# S7CAS-PLEIADES-CARTE-MERE_P01_FPGA-BANK0.net
KiCad netlist of a schematic drawn in Altium Designer
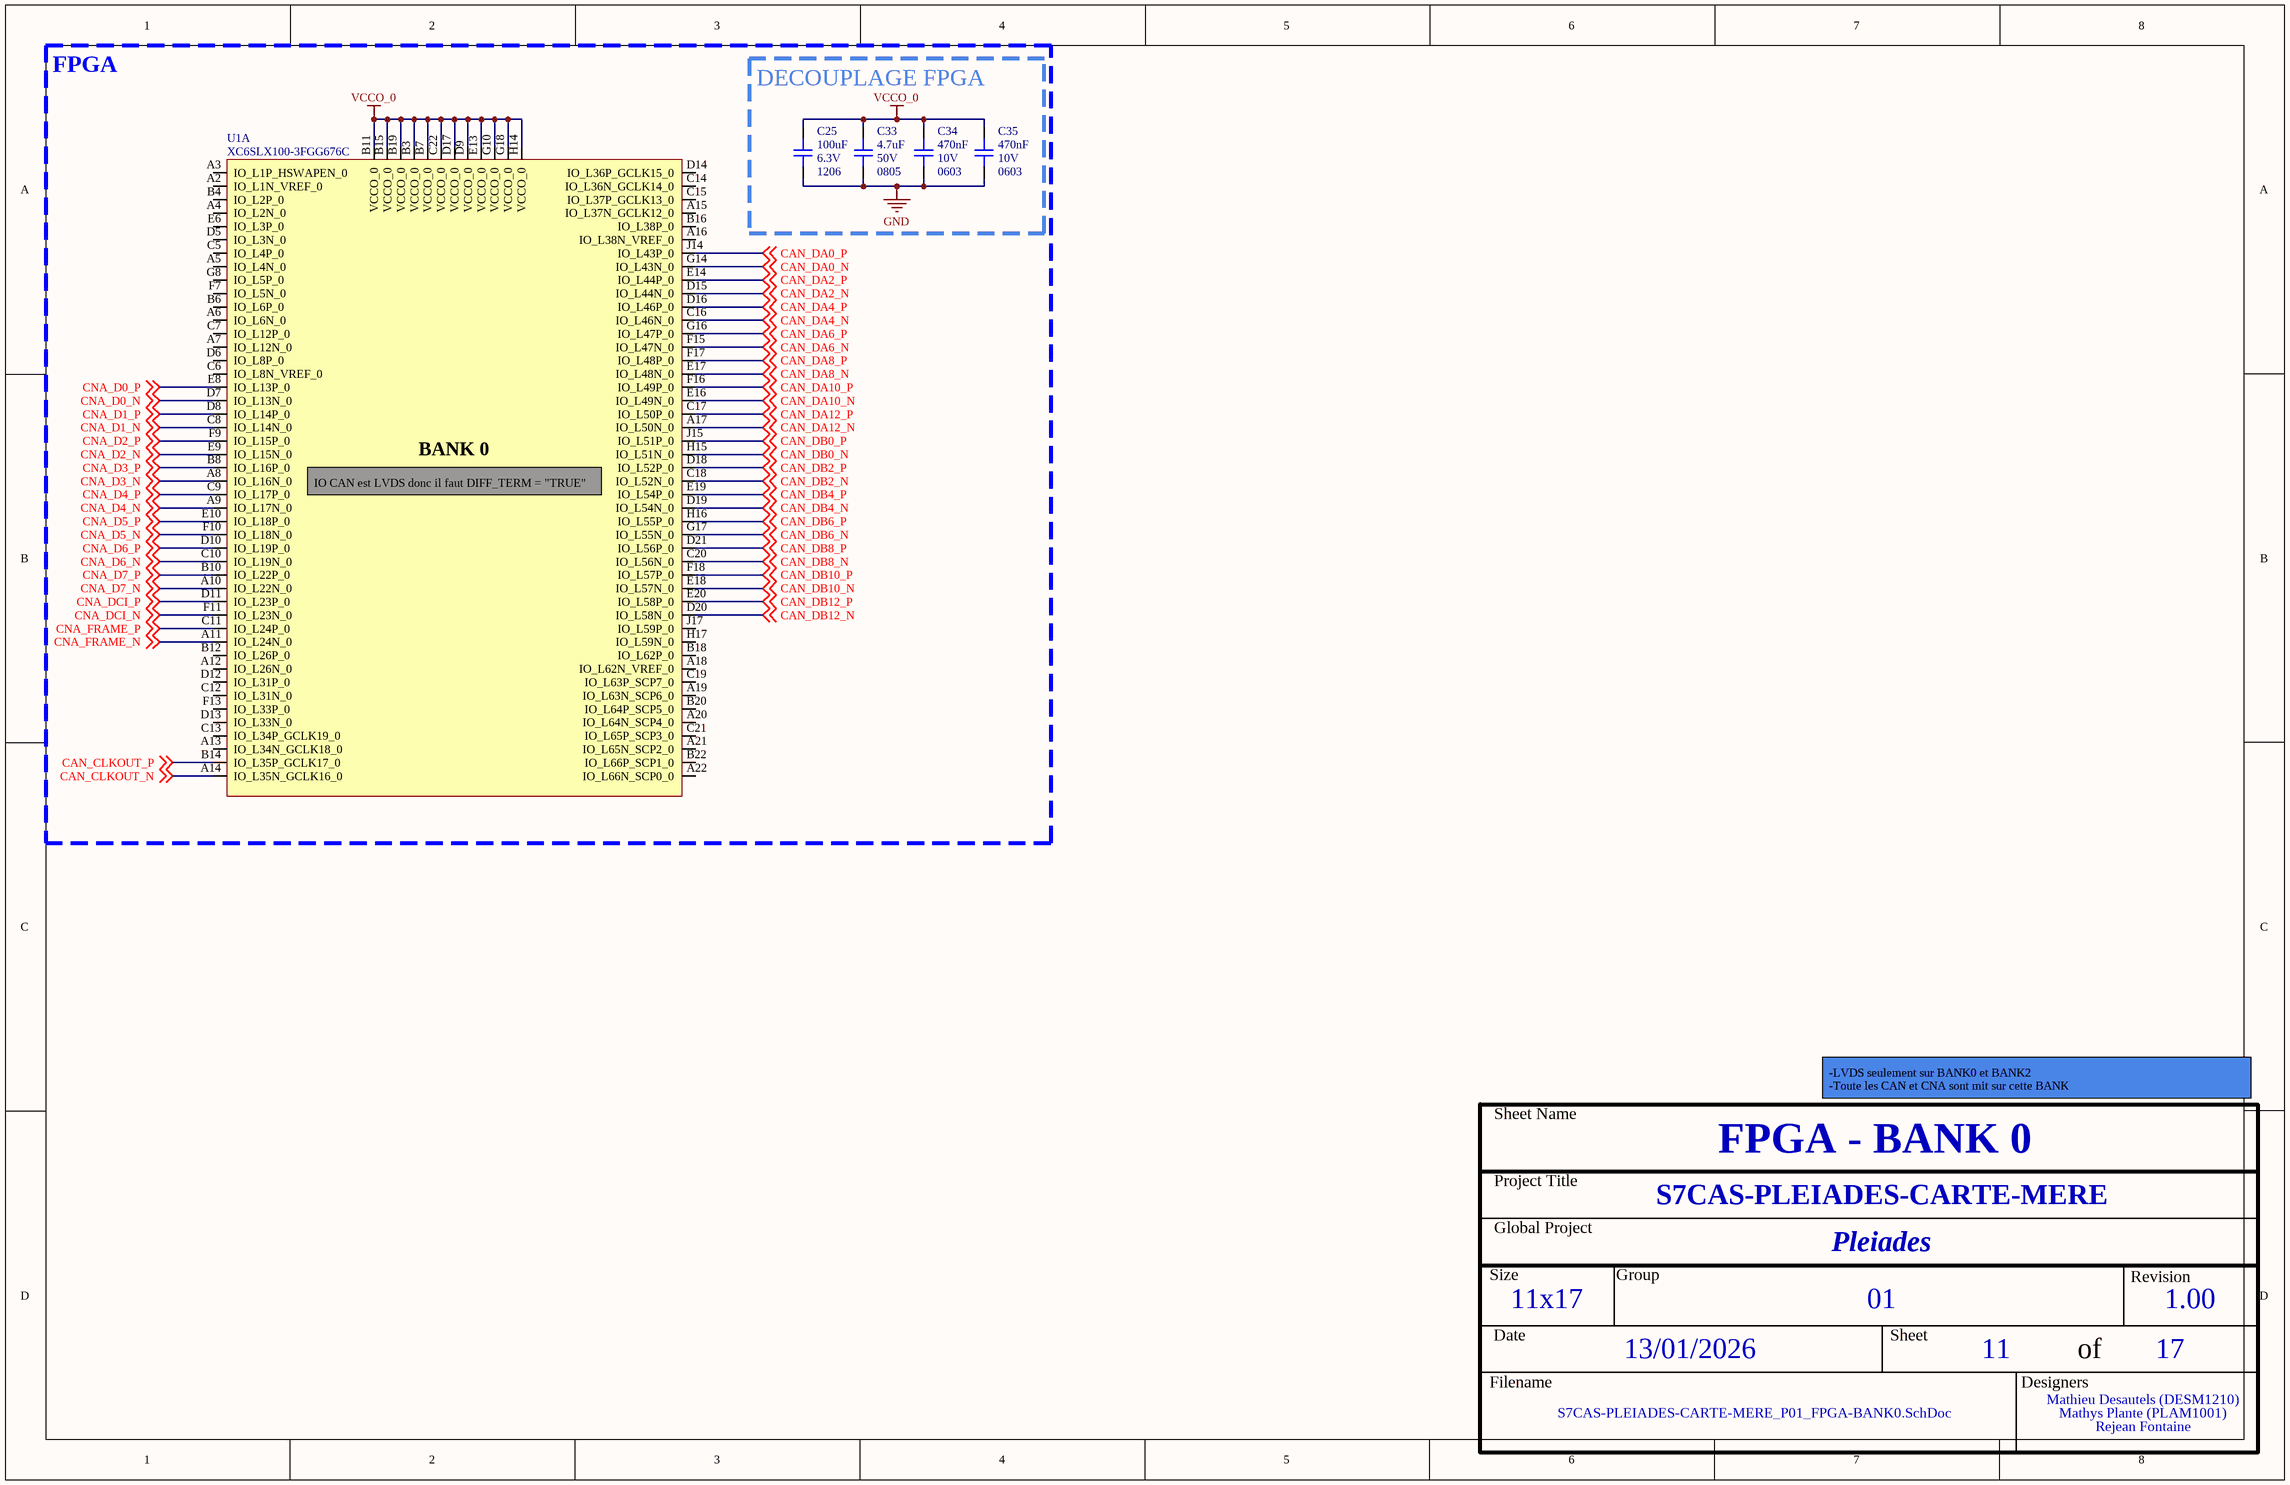
[diagram p0: S7CAS-PLEIADES-CARTE-MERE_P01_FPGA-BANK0.SchDoc]

(export (version "E")
  (design (tool "Eeschema 10.0.6"))
  (components
    (comp (ref "C25")
      (value "100uF")
      (footprint "CAP_1206")
      (description "100 µF ±20% 6.3V Ceramic Capacitor X6T 1206 (3216 Metric)")
      (fields
        (field (name "MFG") "Murata Electronics")
        (field (name "MFG PART NUMBER") "GRM31CD80J107MEA8K")
        (field (name "VOLTAGE") "6.3V")
        (field (name "PACKAGE") "1206")
        (field (name "CREATEDBY") "Jonathan Bouchard")
      )
      (libsource (lib "s7cas_lib2023") (part "CAP - 1206"))
    )
    (comp (ref "C33")
      (value "4.7uF")
      (footprint "CAP_0805")
      (description "4.7 µF ±10% 50V Ceramic Capacitor X5R 0805 (2012 Metric)")
      (fields
        (field (name "MFG") "Murata Electronics")
        (field (name "MFG PART NUMBER") "GRT21BR61H475KE13L")
        (field (name "VOLTAGE") "50V")
        (field (name "PACKAGE") "0805")
        (field (name "CREATEDBY") "Jonathan Bouchard")
      )
      (libsource (lib "s7cas_lib2023") (part "CAP - 0805"))
    )
    (comp (ref "C34")
      (value "470nF")
      (footprint "CAP_0603")
      (description "CAP - 0603")
      (fields
        (field (name "MFG PART NUMBER") "C0603X474K8RAC")
        (field (name "VOLTAGE") "10V")
        (field (name "PACKAGE") "0603")
        (field (name "CREATEDBY") "Jonathan Bouchard")
      )
      (libsource (lib "s7cas_lib2023") (part "CAP - 0603"))
    )
    (comp (ref "C35")
      (value "470nF")
      (footprint "CAP_0603")
      (description "CAP - 0603")
      (fields
        (field (name "MFG PART NUMBER") "C0603X474K8RAC")
        (field (name "VOLTAGE") "10V")
        (field (name "PACKAGE") "0603")
        (field (name "CREATEDBY") "Jonathan Bouchard")
      )
      (libsource (lib "s7cas_lib2023") (part "CAP - 0603"))
    )
    (comp (ref "U1")
      (value "XC6SLX100-3FGG676C")
      (footprint "FPGA_XILINX_FGG676")
      (description "FPGA - XILINX SPARTAN 6 480 I/O - BGA-676")
      (fields
        (field (name "VOLTAGE") "1.14 V ~ 1.26 V")
        (field (name "MFG") "Xilinx")
        (field (name "CREATEDBY") "Jonathan Bouchard")
      )
      (libsource (lib "s7cas_lib2023") (part "FPGA_XC6SLX100-3FGG676C"))
    )
  )
  (nets
    (net (code "1") (name "CAN_CLKOUT_N") (class "Default")
      (node (ref "U1") (pin "A14") (pinfunction "IO_L35N_GCLK16_0_A14") (pintype "passive"))
    )
    (net (code "2") (name "CAN_CLKOUT_P") (class "Default")
      (node (ref "U1") (pin "B14") (pinfunction "IO_L35P_GCLK17_0_B14") (pintype "passive"))
    )
    (net (code "3") (name "CAN_DA0_N") (class "Default")
      (node (ref "U1") (pin "G14") (pinfunction "IO_L43N_0_G14") (pintype "passive"))
    )
    (net (code "4") (name "CAN_DA0_P") (class "Default")
      (node (ref "U1") (pin "J14") (pinfunction "IO_L43P_0_J14") (pintype "passive"))
    )
    (net (code "5") (name "CAN_DA2_N") (class "Default")
      (node (ref "U1") (pin "D15") (pinfunction "IO_L44N_0_D15") (pintype "passive"))
    )
    (net (code "6") (name "CAN_DA2_P") (class "Default")
      (node (ref "U1") (pin "E14") (pinfunction "IO_L44P_0_E14") (pintype "passive"))
    )
    (net (code "7") (name "CAN_DA4_N") (class "Default")
      (node (ref "U1") (pin "C16") (pinfunction "IO_L46N_0_C16") (pintype "passive"))
    )
    (net (code "8") (name "CAN_DA4_P") (class "Default")
      (node (ref "U1") (pin "D16") (pinfunction "IO_L46P_0_D16") (pintype "passive"))
    )
    (net (code "9") (name "CAN_DA6_N") (class "Default")
      (node (ref "U1") (pin "F15") (pinfunction "IO_L47N_0_F15") (pintype "passive"))
    )
    (net (code "10") (name "CAN_DA6_P") (class "Default")
      (node (ref "U1") (pin "G16") (pinfunction "IO_L47P_0_G16") (pintype "passive"))
    )
    (net (code "11") (name "CAN_DA8_N") (class "Default")
      (node (ref "U1") (pin "E17") (pinfunction "IO_L48N_0_E17") (pintype "passive"))
    )
    (net (code "12") (name "CAN_DA8_P") (class "Default")
      (node (ref "U1") (pin "F17") (pinfunction "IO_L48P_0_F17") (pintype "passive"))
    )
    (net (code "13") (name "CAN_DA10_N") (class "Default")
      (node (ref "U1") (pin "E16") (pinfunction "IO_L49N_0_E16") (pintype "passive"))
    )
    (net (code "14") (name "CAN_DA10_P") (class "Default")
      (node (ref "U1") (pin "F16") (pinfunction "IO_L49P_0_F16") (pintype "passive"))
    )
    (net (code "15") (name "CAN_DA12_N") (class "Default")
      (node (ref "U1") (pin "A17") (pinfunction "IO_L50N_0_A17") (pintype "passive"))
    )
    (net (code "16") (name "CAN_DA12_P") (class "Default")
      (node (ref "U1") (pin "C17") (pinfunction "IO_L50P_0_C17") (pintype "passive"))
    )
    (net (code "17") (name "CAN_DB0_N") (class "Default")
      (node (ref "U1") (pin "H15") (pinfunction "IO_L51N_0_H15") (pintype "passive"))
    )
    (net (code "18") (name "CAN_DB0_P") (class "Default")
      (node (ref "U1") (pin "J15") (pinfunction "IO_L51P_0_J15") (pintype "passive"))
    )
    (net (code "19") (name "CAN_DB2_N") (class "Default")
      (node (ref "U1") (pin "C18") (pinfunction "IO_L52N_0_C18") (pintype "passive"))
    )
    (net (code "20") (name "CAN_DB2_P") (class "Default")
      (node (ref "U1") (pin "D18") (pinfunction "IO_L52P_0_D18") (pintype "passive"))
    )
    (net (code "21") (name "CAN_DB4_N") (class "Default")
      (node (ref "U1") (pin "D19") (pinfunction "IO_L54N_0_D19") (pintype "passive"))
    )
    (net (code "22") (name "CAN_DB4_P") (class "Default")
      (node (ref "U1") (pin "E19") (pinfunction "IO_L54P_0_E19") (pintype "passive"))
    )
    (net (code "23") (name "CAN_DB6_N") (class "Default")
      (node (ref "U1") (pin "G17") (pinfunction "IO_L55N_0_G17") (pintype "passive"))
    )
    (net (code "24") (name "CAN_DB6_P") (class "Default")
      (node (ref "U1") (pin "H16") (pinfunction "IO_L55P_0_H16") (pintype "passive"))
    )
    (net (code "25") (name "CAN_DB8_N") (class "Default")
      (node (ref "U1") (pin "C20") (pinfunction "IO_L56N_0_C20") (pintype "passive"))
    )
    (net (code "26") (name "CAN_DB8_P") (class "Default")
      (node (ref "U1") (pin "D21") (pinfunction "IO_L56P_0_D21") (pintype "passive"))
    )
    (net (code "27") (name "CAN_DB10_N") (class "Default")
      (node (ref "U1") (pin "E18") (pinfunction "IO_L57N_0_E18") (pintype "passive"))
    )
    (net (code "28") (name "CAN_DB10_P") (class "Default")
      (node (ref "U1") (pin "F18") (pinfunction "IO_L57P_0_F18") (pintype "passive"))
    )
    (net (code "29") (name "CAN_DB12_N") (class "Default")
      (node (ref "U1") (pin "D20") (pinfunction "IO_L58N_0_D20") (pintype "passive"))
    )
    (net (code "30") (name "CAN_DB12_P") (class "Default")
      (node (ref "U1") (pin "E20") (pinfunction "IO_L58P_0_E20") (pintype "passive"))
    )
    (net (code "31") (name "CNA_D0_N") (class "Default")
      (node (ref "U1") (pin "D7") (pinfunction "IO_L13N_0_D7") (pintype "passive"))
    )
    (net (code "32") (name "CNA_D0_P") (class "Default")
      (node (ref "U1") (pin "E8") (pinfunction "IO_L13P_0_E8") (pintype "passive"))
    )
    (net (code "33") (name "CNA_D1_N") (class "Default")
      (node (ref "U1") (pin "C8") (pinfunction "IO_L14N_0_C8") (pintype "passive"))
    )
    (net (code "34") (name "CNA_D1_P") (class "Default")
      (node (ref "U1") (pin "D8") (pinfunction "IO_L14P_0_D8") (pintype "passive"))
    )
    (net (code "35") (name "CNA_D2_N") (class "Default")
      (node (ref "U1") (pin "E9") (pinfunction "IO_L15N_0_E9") (pintype "passive"))
    )
    (net (code "36") (name "CNA_D2_P") (class "Default")
      (node (ref "U1") (pin "F9") (pinfunction "IO_L15P_0_F9") (pintype "passive"))
    )
    (net (code "37") (name "CNA_D3_N") (class "Default")
      (node (ref "U1") (pin "A8") (pinfunction "IO_L16N_0_A8") (pintype "passive"))
    )
    (net (code "38") (name "CNA_D3_P") (class "Default")
      (node (ref "U1") (pin "B8") (pinfunction "IO_L16P_0_B8") (pintype "passive"))
    )
    (net (code "39") (name "CNA_D4_N") (class "Default")
      (node (ref "U1") (pin "A9") (pinfunction "IO_L17N_0_A9") (pintype "passive"))
    )
    (net (code "40") (name "CNA_D4_P") (class "Default")
      (node (ref "U1") (pin "C9") (pinfunction "IO_L17P_0_C9") (pintype "passive"))
    )
    (net (code "41") (name "CNA_D5_N") (class "Default")
      (node (ref "U1") (pin "F10") (pinfunction "IO_L18N_0_F10") (pintype "passive"))
    )
    (net (code "42") (name "CNA_D5_P") (class "Default")
      (node (ref "U1") (pin "E10") (pinfunction "IO_L18P_0_E10") (pintype "passive"))
    )
    (net (code "43") (name "CNA_D6_N") (class "Default")
      (node (ref "U1") (pin "C10") (pinfunction "IO_L19N_0_C10") (pintype "passive"))
    )
    (net (code "44") (name "CNA_D6_P") (class "Default")
      (node (ref "U1") (pin "D10") (pinfunction "IO_L19P_0_D10") (pintype "passive"))
    )
    (net (code "45") (name "CNA_D7_N") (class "Default")
      (node (ref "U1") (pin "A10") (pinfunction "IO_L22N_0_A10") (pintype "passive"))
    )
    (net (code "46") (name "CNA_D7_P") (class "Default")
      (node (ref "U1") (pin "B10") (pinfunction "IO_L22P_0_B10") (pintype "passive"))
    )
    (net (code "47") (name "CNA_DCI_N") (class "Default")
      (node (ref "U1") (pin "F11") (pinfunction "IO_L23N_0_F11") (pintype "passive"))
    )
    (net (code "48") (name "CNA_DCI_P") (class "Default")
      (node (ref "U1") (pin "D11") (pinfunction "IO_L23P_0_D11") (pintype "passive"))
    )
    (net (code "49") (name "CNA_FRAME_N") (class "Default")
      (node (ref "U1") (pin "A11") (pinfunction "IO_L24N_0_A11") (pintype "passive"))
    )
    (net (code "50") (name "CNA_FRAME_P") (class "Default")
      (node (ref "U1") (pin "C11") (pinfunction "IO_L24P_0_C11") (pintype "passive"))
    )
    (net (code "51") (name "GND") (class "Default")
      (node (ref "C25") (pin "1") (pinfunction "1_1") (pintype "passive"))
      (node (ref "C33") (pin "1") (pinfunction "1_1") (pintype "passive"))
      (node (ref "C34") (pin "1") (pinfunction "1_1") (pintype "passive"))
      (node (ref "C35") (pin "1") (pinfunction "1_1") (pintype "passive"))
    )
    (net (code "52") (name "VCCO_0") (class "Default")
      (node (ref "C25") (pin "2") (pinfunction "2_2") (pintype "passive"))
      (node (ref "C33") (pin "2") (pinfunction "2_2") (pintype "passive"))
      (node (ref "C34") (pin "2") (pinfunction "2_2") (pintype "passive"))
      (node (ref "C35") (pin "2") (pinfunction "2_2") (pintype "passive"))
      (node (ref "U1") (pin "B11") (pinfunction "VCCO_0_B11") (pintype "passive"))
      (node (ref "U1") (pin "B15") (pinfunction "VCCO_0_B15") (pintype "passive"))
      (node (ref "U1") (pin "B19") (pinfunction "VCCO_0_B19") (pintype "passive"))
      (node (ref "U1") (pin "B3") (pinfunction "VCCO_0_B3") (pintype "passive"))
      (node (ref "U1") (pin "B7") (pinfunction "VCCO_0_B7") (pintype "passive"))
      (node (ref "U1") (pin "C22") (pinfunction "VCCO_0_C22") (pintype "passive"))
      (node (ref "U1") (pin "D17") (pinfunction "VCCO_0_D17") (pintype "passive"))
      (node (ref "U1") (pin "D9") (pinfunction "VCCO_0_D9") (pintype "passive"))
      (node (ref "U1") (pin "E13") (pinfunction "VCCO_0_E13") (pintype "passive"))
      (node (ref "U1") (pin "G10") (pinfunction "VCCO_0_G10") (pintype "passive"))
      (node (ref "U1") (pin "G18") (pinfunction "VCCO_0_G18") (pintype "passive"))
      (node (ref "U1") (pin "H14") (pinfunction "VCCO_0_H14") (pintype "passive"))
    )
    (net (code "53") (name "unconnected-(U1A-IO_L1N_VREF_0-PadA2)") (class "Default")
      (node (ref "U1") (pin "A2") (pinfunction "IO_L1N_VREF_0_A2") (pintype "passive"))
    )
    (net (code "54") (name "unconnected-(U1A-IO_L1P_HSWAPEN_0-PadA3)") (class "Default")
      (node (ref "U1") (pin "A3") (pinfunction "IO_L1P_HSWAPEN_0_A3") (pintype "passive"))
    )
    (net (code "55") (name "unconnected-(U1A-IO_L2N_0-PadA4)") (class "Default")
      (node (ref "U1") (pin "A4") (pinfunction "IO_L2N_0_A4") (pintype "passive"))
    )
    (net (code "56") (name "unconnected-(U1A-IO_L2P_0-PadB4)") (class "Default")
      (node (ref "U1") (pin "B4") (pinfunction "IO_L2P_0_B4") (pintype "passive"))
    )
    (net (code "57") (name "unconnected-(U1A-IO_L3N_0-PadD5)") (class "Default")
      (node (ref "U1") (pin "D5") (pinfunction "IO_L3N_0_D5") (pintype "passive"))
    )
    (net (code "58") (name "unconnected-(U1A-IO_L3P_0-PadE6)") (class "Default")
      (node (ref "U1") (pin "E6") (pinfunction "IO_L3P_0_E6") (pintype "passive"))
    )
    (net (code "59") (name "unconnected-(U1A-IO_L4N_0-PadA5)") (class "Default")
      (node (ref "U1") (pin "A5") (pinfunction "IO_L4N_0_A5") (pintype "passive"))
    )
    (net (code "60") (name "unconnected-(U1A-IO_L4P_0-PadC5)") (class "Default")
      (node (ref "U1") (pin "C5") (pinfunction "IO_L4P_0_C5") (pintype "passive"))
    )
    (net (code "61") (name "unconnected-(U1A-IO_L5N_0-PadF7)") (class "Default")
      (node (ref "U1") (pin "F7") (pinfunction "IO_L5N_0_F7") (pintype "passive"))
    )
    (net (code "62") (name "unconnected-(U1A-IO_L5P_0-PadG8)") (class "Default")
      (node (ref "U1") (pin "G8") (pinfunction "IO_L5P_0_G8") (pintype "passive"))
    )
    (net (code "63") (name "unconnected-(U1A-IO_L6N_0-PadA6)") (class "Default")
      (node (ref "U1") (pin "A6") (pinfunction "IO_L6N_0_A6") (pintype "passive"))
    )
    (net (code "64") (name "unconnected-(U1A-IO_L6P_0-PadB6)") (class "Default")
      (node (ref "U1") (pin "B6") (pinfunction "IO_L6P_0_B6") (pintype "passive"))
    )
    (net (code "65") (name "unconnected-(U1A-IO_L8N_VREF_0-PadC6)") (class "Default")
      (node (ref "U1") (pin "C6") (pinfunction "IO_L8N_VREF_0_C6") (pintype "passive"))
    )
    (net (code "66") (name "unconnected-(U1A-IO_L8P_0-PadD6)") (class "Default")
      (node (ref "U1") (pin "D6") (pinfunction "IO_L8P_0_D6") (pintype "passive"))
    )
    (net (code "67") (name "unconnected-(U1A-IO_L12N_0-PadA7)") (class "Default")
      (node (ref "U1") (pin "A7") (pinfunction "IO_L12N_0_A7") (pintype "passive"))
    )
    (net (code "68") (name "unconnected-(U1A-IO_L12P_0-PadC7)") (class "Default")
      (node (ref "U1") (pin "C7") (pinfunction "IO_L12P_0_C7") (pintype "passive"))
    )
    (net (code "69") (name "unconnected-(U1A-IO_L26N_0-PadA12)") (class "Default")
      (node (ref "U1") (pin "A12") (pinfunction "IO_L26N_0_A12") (pintype "passive"))
    )
    (net (code "70") (name "unconnected-(U1A-IO_L26P_0-PadB12)") (class "Default")
      (node (ref "U1") (pin "B12") (pinfunction "IO_L26P_0_B12") (pintype "passive"))
    )
    (net (code "71") (name "unconnected-(U1A-IO_L31N_0-PadC12)") (class "Default")
      (node (ref "U1") (pin "C12") (pinfunction "IO_L31N_0_C12") (pintype "passive"))
    )
    (net (code "72") (name "unconnected-(U1A-IO_L31P_0-PadD12)") (class "Default")
      (node (ref "U1") (pin "D12") (pinfunction "IO_L31P_0_D12") (pintype "passive"))
    )
    (net (code "73") (name "unconnected-(U1A-IO_L33N_0-PadD13)") (class "Default")
      (node (ref "U1") (pin "D13") (pinfunction "IO_L33N_0_D13") (pintype "passive"))
    )
    (net (code "74") (name "unconnected-(U1A-IO_L33P_0-PadF13)") (class "Default")
      (node (ref "U1") (pin "F13") (pinfunction "IO_L33P_0_F13") (pintype "passive"))
    )
    (net (code "75") (name "unconnected-(U1A-IO_L34N_GCLK18_0-PadA13)") (class "Default")
      (node (ref "U1") (pin "A13") (pinfunction "IO_L34N_GCLK18_0_A13") (pintype "passive"))
    )
    (net (code "76") (name "unconnected-(U1A-IO_L34P_GCLK19_0-PadC13)") (class "Default")
      (node (ref "U1") (pin "C13") (pinfunction "IO_L34P_GCLK19_0_C13") (pintype "passive"))
    )
    (net (code "77") (name "unconnected-(U1A-IO_L36N_GCLK14_0-PadC14)") (class "Default")
      (node (ref "U1") (pin "C14") (pinfunction "IO_L36N_GCLK14_0_C14") (pintype "passive"))
    )
    (net (code "78") (name "unconnected-(U1A-IO_L36P_GCLK15_0-PadD14)") (class "Default")
      (node (ref "U1") (pin "D14") (pinfunction "IO_L36P_GCLK15_0_D14") (pintype "passive"))
    )
    (net (code "79") (name "unconnected-(U1A-IO_L37N_GCLK12_0-PadA15)") (class "Default")
      (node (ref "U1") (pin "A15") (pinfunction "IO_L37N_GCLK12_0_A15") (pintype "passive"))
    )
    (net (code "80") (name "unconnected-(U1A-IO_L37P_GCLK13_0-PadC15)") (class "Default")
      (node (ref "U1") (pin "C15") (pinfunction "IO_L37P_GCLK13_0_C15") (pintype "passive"))
    )
    (net (code "81") (name "unconnected-(U1A-IO_L38N_VREF_0-PadA16)") (class "Default")
      (node (ref "U1") (pin "A16") (pinfunction "IO_L38N_VREF_0_A16") (pintype "passive"))
    )
    (net (code "82") (name "unconnected-(U1A-IO_L38P_0-PadB16)") (class "Default")
      (node (ref "U1") (pin "B16") (pinfunction "IO_L38P_0_B16") (pintype "passive"))
    )
    (net (code "83") (name "unconnected-(U1A-IO_L59N_0-PadH17)") (class "Default")
      (node (ref "U1") (pin "H17") (pinfunction "IO_L59N_0_H17") (pintype "passive"))
    )
    (net (code "84") (name "unconnected-(U1A-IO_L59P_0-PadJ17)") (class "Default")
      (node (ref "U1") (pin "J17") (pinfunction "IO_L59P_0_J17") (pintype "passive"))
    )
    (net (code "85") (name "unconnected-(U1A-IO_L62N_VREF_0-PadA18)") (class "Default")
      (node (ref "U1") (pin "A18") (pinfunction "IO_L62N_VREF_0_A18") (pintype "passive"))
    )
    (net (code "86") (name "unconnected-(U1A-IO_L62P_0-PadB18)") (class "Default")
      (node (ref "U1") (pin "B18") (pinfunction "IO_L62P_0_B18") (pintype "passive"))
    )
    (net (code "87") (name "unconnected-(U1A-IO_L63N_SCP6_0-PadA19)") (class "Default")
      (node (ref "U1") (pin "A19") (pinfunction "IO_L63N_SCP6_0_A19") (pintype "passive"))
    )
    (net (code "88") (name "unconnected-(U1A-IO_L63P_SCP7_0-PadC19)") (class "Default")
      (node (ref "U1") (pin "C19") (pinfunction "IO_L63P_SCP7_0_C19") (pintype "passive"))
    )
    (net (code "89") (name "unconnected-(U1A-IO_L64N_SCP4_0-PadA20)") (class "Default")
      (node (ref "U1") (pin "A20") (pinfunction "IO_L64N_SCP4_0_A20") (pintype "passive"))
    )
    (net (code "90") (name "unconnected-(U1A-IO_L64P_SCP5_0-PadB20)") (class "Default")
      (node (ref "U1") (pin "B20") (pinfunction "IO_L64P_SCP5_0_B20") (pintype "passive"))
    )
    (net (code "91") (name "unconnected-(U1A-IO_L65N_SCP2_0-PadA21)") (class "Default")
      (node (ref "U1") (pin "A21") (pinfunction "IO_L65N_SCP2_0_A21") (pintype "passive"))
    )
    (net (code "92") (name "unconnected-(U1A-IO_L65P_SCP3_0-PadC21)") (class "Default")
      (node (ref "U1") (pin "C21") (pinfunction "IO_L65P_SCP3_0_C21") (pintype "passive"))
    )
    (net (code "93") (name "unconnected-(U1A-IO_L66N_SCP0_0-PadA22)") (class "Default")
      (node (ref "U1") (pin "A22") (pinfunction "IO_L66N_SCP0_0_A22") (pintype "passive"))
    )
    (net (code "94") (name "unconnected-(U1A-IO_L66P_SCP1_0-PadB22)") (class "Default")
      (node (ref "U1") (pin "B22") (pinfunction "IO_L66P_SCP1_0_B22") (pintype "passive"))
    )
  )
)
